# BitBeacon.net
KiCad netlist of a schematic drawn in EAGLE
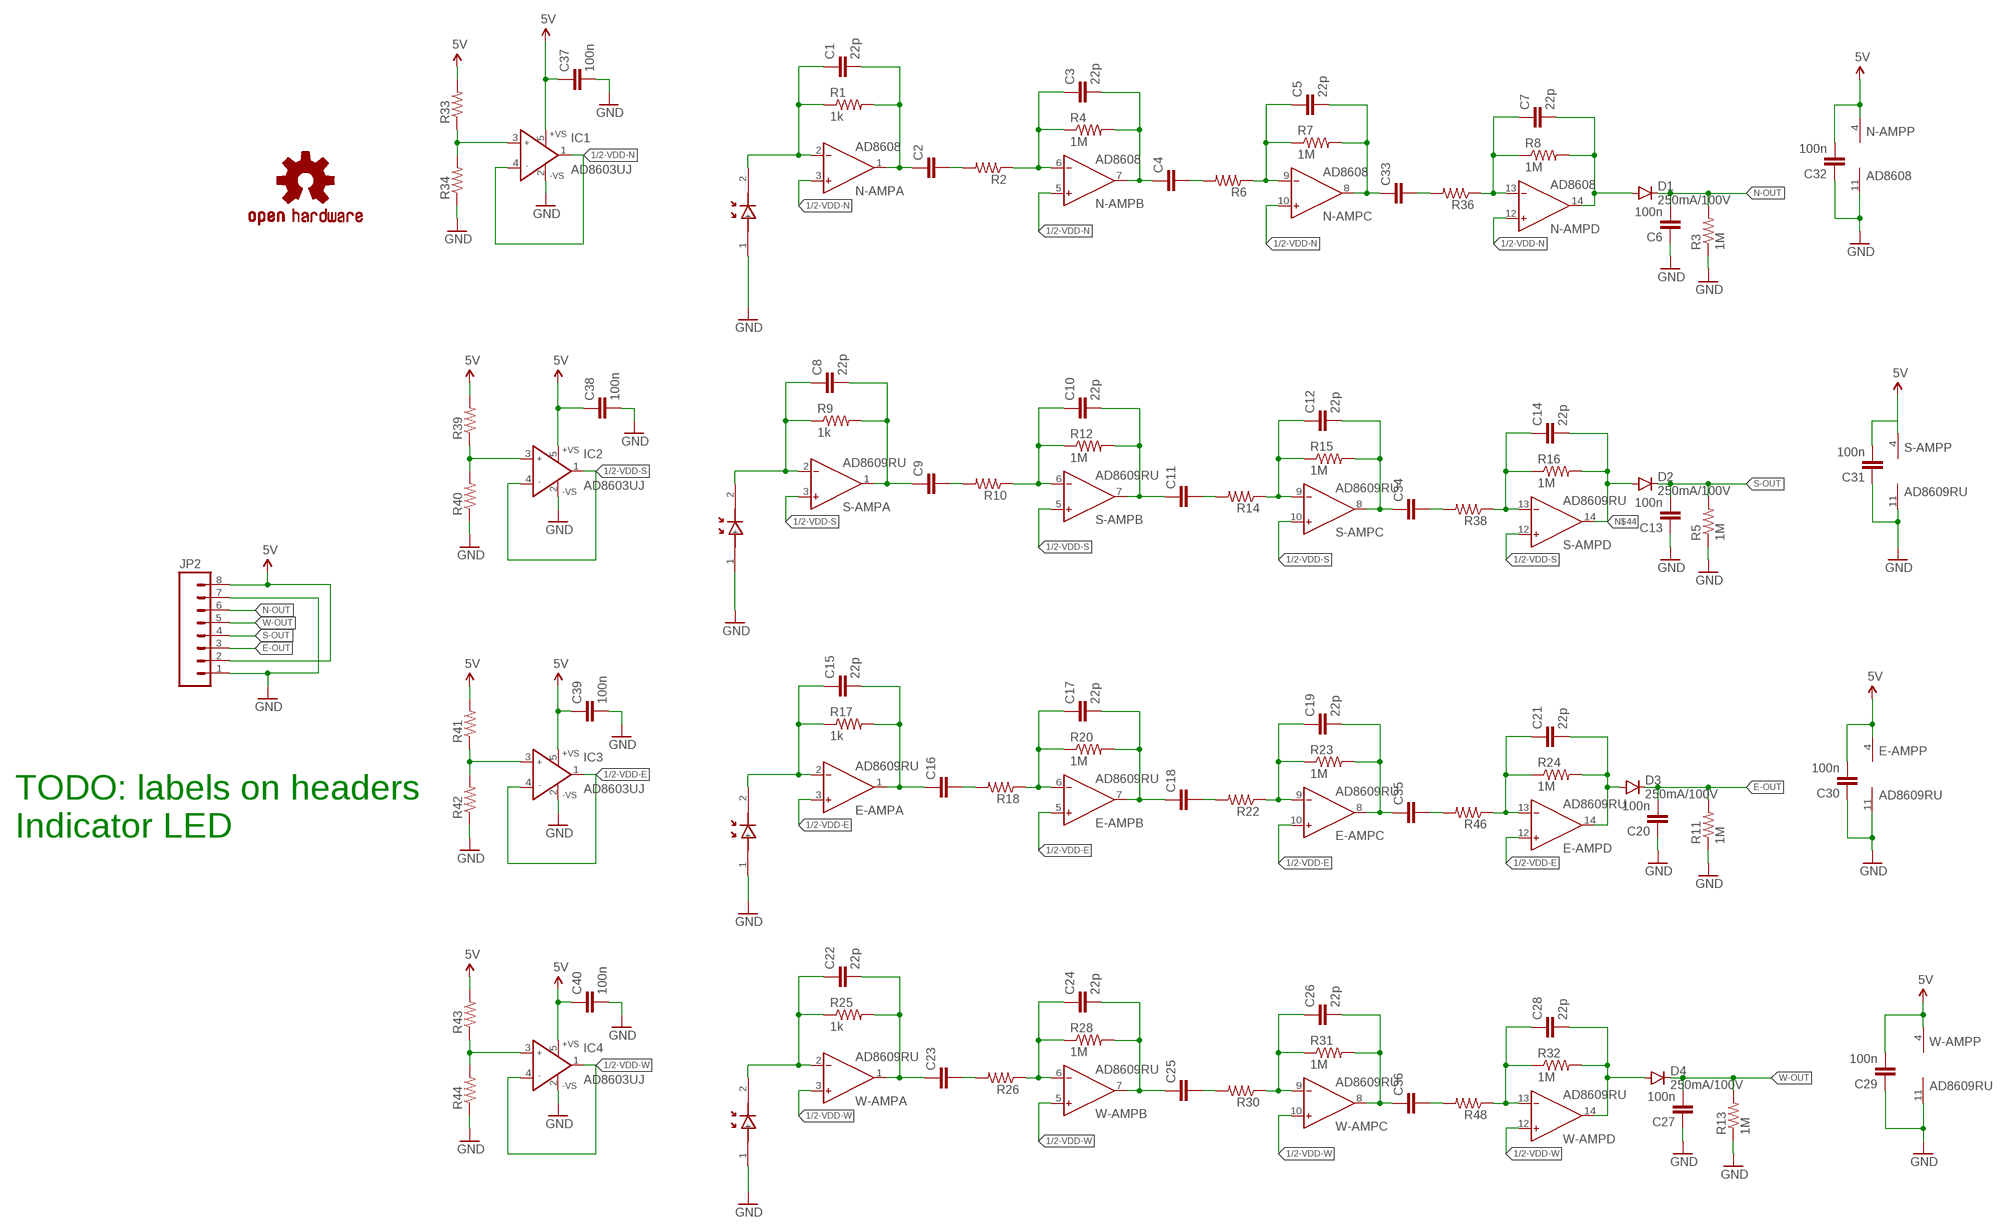
[diagram p0: schematic, sheet 1]

(export (version "E")
  (design (tool "Eeschema 10.0.6"))
  (components
    (comp (ref "C1")
      (value "22p")
      (footprint "eagle-import:C0402")
      (libsource (lib "eagle-import") (part "C-EUC0402"))
    )
    (comp (ref "C2")
      (value "C-EUC0402")
      (footprint "eagle-import:C0402")
      (libsource (lib "eagle-import") (part "C-EUC0402"))
    )
    (comp (ref "C3")
      (value "22p")
      (footprint "eagle-import:C0402")
      (libsource (lib "eagle-import") (part "C-EUC0402"))
    )
    (comp (ref "C4")
      (value "C-EUC0402")
      (footprint "eagle-import:C0402")
      (libsource (lib "eagle-import") (part "C-EUC0402"))
    )
    (comp (ref "C5")
      (value "22p")
      (footprint "eagle-import:C0402")
      (libsource (lib "eagle-import") (part "C-EUC0402"))
    )
    (comp (ref "C6")
      (value "100n")
      (footprint "eagle-import:C0402")
      (libsource (lib "eagle-import") (part "C-EUC0402"))
    )
    (comp (ref "C7")
      (value "22p")
      (footprint "eagle-import:C0402")
      (libsource (lib "eagle-import") (part "C-EUC0402"))
    )
    (comp (ref "C8")
      (value "22p")
      (footprint "eagle-import:C0402")
      (libsource (lib "eagle-import") (part "C-EUC0402"))
    )
    (comp (ref "C9")
      (value "C-EUC0402")
      (footprint "eagle-import:C0402")
      (libsource (lib "eagle-import") (part "C-EUC0402"))
    )
    (comp (ref "C10")
      (value "22p")
      (footprint "eagle-import:C0402")
      (libsource (lib "eagle-import") (part "C-EUC0402"))
    )
    (comp (ref "C11")
      (value "C-EUC0402")
      (footprint "eagle-import:C0402")
      (libsource (lib "eagle-import") (part "C-EUC0402"))
    )
    (comp (ref "C12")
      (value "22p")
      (footprint "eagle-import:C0402")
      (libsource (lib "eagle-import") (part "C-EUC0402"))
    )
    (comp (ref "C13")
      (value "100n")
      (footprint "eagle-import:C0402")
      (libsource (lib "eagle-import") (part "C-EUC0402"))
    )
    (comp (ref "C14")
      (value "22p")
      (footprint "eagle-import:C0402")
      (libsource (lib "eagle-import") (part "C-EUC0402"))
    )
    (comp (ref "C15")
      (value "22p")
      (footprint "eagle-import:C0402")
      (libsource (lib "eagle-import") (part "C-EUC0402"))
    )
    (comp (ref "C16")
      (value "C-EUC0402")
      (footprint "eagle-import:C0402")
      (libsource (lib "eagle-import") (part "C-EUC0402"))
    )
    (comp (ref "C17")
      (value "22p")
      (footprint "eagle-import:C0402")
      (libsource (lib "eagle-import") (part "C-EUC0402"))
    )
    (comp (ref "C18")
      (value "C-EUC0402")
      (footprint "eagle-import:C0402")
      (libsource (lib "eagle-import") (part "C-EUC0402"))
    )
    (comp (ref "C19")
      (value "22p")
      (footprint "eagle-import:C0402")
      (libsource (lib "eagle-import") (part "C-EUC0402"))
    )
    (comp (ref "C20")
      (value "100n")
      (footprint "eagle-import:C0402")
      (libsource (lib "eagle-import") (part "C-EUC0402"))
    )
    (comp (ref "C21")
      (value "22p")
      (footprint "eagle-import:C0402")
      (libsource (lib "eagle-import") (part "C-EUC0402"))
    )
    (comp (ref "C22")
      (value "22p")
      (footprint "eagle-import:C0402")
      (libsource (lib "eagle-import") (part "C-EUC0402"))
    )
    (comp (ref "C23")
      (value "C-EUC0402")
      (footprint "eagle-import:C0402")
      (libsource (lib "eagle-import") (part "C-EUC0402"))
    )
    (comp (ref "C24")
      (value "22p")
      (footprint "eagle-import:C0402")
      (libsource (lib "eagle-import") (part "C-EUC0402"))
    )
    (comp (ref "C25")
      (value "C-EUC0402")
      (footprint "eagle-import:C0402")
      (libsource (lib "eagle-import") (part "C-EUC0402"))
    )
    (comp (ref "C26")
      (value "22p")
      (footprint "eagle-import:C0402")
      (libsource (lib "eagle-import") (part "C-EUC0402"))
    )
    (comp (ref "C27")
      (value "100n")
      (footprint "eagle-import:C0402")
      (libsource (lib "eagle-import") (part "C-EUC0402"))
    )
    (comp (ref "C28")
      (value "22p")
      (footprint "eagle-import:C0402")
      (libsource (lib "eagle-import") (part "C-EUC0402"))
    )
    (comp (ref "C29")
      (value "100n")
      (footprint "eagle-import:C0402")
      (libsource (lib "eagle-import") (part "C-EUC0402"))
    )
    (comp (ref "C30")
      (value "100n")
      (footprint "eagle-import:C0402")
      (libsource (lib "eagle-import") (part "C-EUC0402"))
    )
    (comp (ref "C31")
      (value "100n")
      (footprint "eagle-import:C0402")
      (libsource (lib "eagle-import") (part "C-EUC0402"))
    )
    (comp (ref "C32")
      (value "100n")
      (footprint "eagle-import:C0402")
      (libsource (lib "eagle-import") (part "C-EUC0402"))
    )
    (comp (ref "C33")
      (value "C-EUC0402")
      (footprint "eagle-import:C0402")
      (libsource (lib "eagle-import") (part "C-EUC0402"))
    )
    (comp (ref "C34")
      (value "C-EUC0402")
      (footprint "eagle-import:C0402")
      (libsource (lib "eagle-import") (part "C-EUC0402"))
    )
    (comp (ref "C35")
      (value "C-EUC0402")
      (footprint "eagle-import:C0402")
      (libsource (lib "eagle-import") (part "C-EUC0402"))
    )
    (comp (ref "C36")
      (value "C-EUC0402")
      (footprint "eagle-import:C0402")
      (libsource (lib "eagle-import") (part "C-EUC0402"))
    )
    (comp (ref "C37")
      (value "100n")
      (footprint "eagle-import:C0402")
      (libsource (lib "eagle-import") (part "C-EUC0402"))
    )
    (comp (ref "C38")
      (value "100n")
      (footprint "eagle-import:C0402")
      (libsource (lib "eagle-import") (part "C-EUC0402"))
    )
    (comp (ref "C39")
      (value "100n")
      (footprint "eagle-import:C0402")
      (libsource (lib "eagle-import") (part "C-EUC0402"))
    )
    (comp (ref "C40")
      (value "100n")
      (footprint "eagle-import:C0402")
      (libsource (lib "eagle-import") (part "C-EUC0402"))
    )
    (comp (ref "D1")
      (value "250mA/100V")
      (footprint "eagle-import:SOD-323")
      (libsource (lib "eagle-import") (part "DIODEBAS16"))
    )
    (comp (ref "D2")
      (value "250mA/100V")
      (footprint "eagle-import:SOD-323")
      (libsource (lib "eagle-import") (part "DIODEBAS16"))
    )
    (comp (ref "D3")
      (value "250mA/100V")
      (footprint "eagle-import:SOD-323")
      (libsource (lib "eagle-import") (part "DIODEBAS16"))
    )
    (comp (ref "D4")
      (value "250mA/100V")
      (footprint "eagle-import:SOD-323")
      (libsource (lib "eagle-import") (part "DIODEBAS16"))
    )
    (comp (ref "E-AMP")
      (value "AD8609RU")
      (footprint "eagle-import:TSSOP14")
      (fields (field (name "MF") "ALTERA CORPORATION") (field (name "MPN") "AD8609ARUZ"))
      (libsource (lib "eagle-import") (part "AD8609RU"))
    )
    (comp (ref "E-PD1")
      (value "BPW46")
      (footprint "eagle-import:PIN-PHOTODIODE")
      (libsource (lib "eagle-import") (part "BPW46"))
    )
    (comp (ref "IC1")
      (value "AD8603UJ")
      (footprint "eagle-import:SOT23-5")
      (fields (field (name "MF") "ALTERA CORPORATION") (field (name "MPN") "AD8603AUJZ-REEL7"))
      (libsource (lib "eagle-import") (part "AD8603UJ"))
    )
    (comp (ref "IC2")
      (value "AD8603UJ")
      (footprint "eagle-import:SOT23-5")
      (fields (field (name "MF") "ALTERA CORPORATION") (field (name "MPN") "AD8603AUJZ-REEL7"))
      (libsource (lib "eagle-import") (part "AD8603UJ"))
    )
    (comp (ref "IC3")
      (value "AD8603UJ")
      (footprint "eagle-import:SOT23-5")
      (fields (field (name "MF") "ALTERA CORPORATION") (field (name "MPN") "AD8603AUJZ-REEL7"))
      (libsource (lib "eagle-import") (part "AD8603UJ"))
    )
    (comp (ref "IC4")
      (value "AD8603UJ")
      (footprint "eagle-import:SOT23-5")
      (fields (field (name "MF") "ALTERA CORPORATION") (field (name "MPN") "AD8603AUJZ-REEL7"))
      (libsource (lib "eagle-import") (part "AD8603UJ"))
    )
    (comp (ref "JP2")
      (value "M08NO_SILK")
      (footprint "eagle-import:1X08_PIN1_NO_SILK")
      (libsource (lib "eagle-import") (part "M08NO_SILK"))
    )
    (comp (ref "LOGO1")
      (value "OSHW-LOGOS")
      (footprint "eagle-import:OSHW-LOGO-S")
      (libsource (lib "eagle-import") (part "OSHW-LOGOS"))
    )
    (comp (ref "N-AMP")
      (value "AD8608")
      (footprint "eagle-import:TSSOP14")
      (fields (field (name "MF") "ALTERA CORPORATION") (field (name "MPN") "AD8609ARUZ"))
      (libsource (lib "eagle-import") (part "AD8609RU"))
    )
    (comp (ref "N-PD1")
      (value "BPW46")
      (footprint "eagle-import:PIN-PHOTODIODE")
      (libsource (lib "eagle-import") (part "BPW46"))
    )
    (comp (ref "R1")
      (value "1k")
      (footprint "eagle-import:R0402")
      (libsource (lib "eagle-import") (part "R-US_R0402"))
    )
    (comp (ref "R2")
      (value "R-US_R0402")
      (footprint "eagle-import:R0402")
      (libsource (lib "eagle-import") (part "R-US_R0402"))
    )
    (comp (ref "R3")
      (value "1M")
      (footprint "eagle-import:R0402")
      (libsource (lib "eagle-import") (part "R-US_R0402"))
    )
    (comp (ref "R4")
      (value "1M")
      (footprint "eagle-import:R0402")
      (libsource (lib "eagle-import") (part "R-US_R0402"))
    )
    (comp (ref "R5")
      (value "1M")
      (footprint "eagle-import:R0402")
      (libsource (lib "eagle-import") (part "R-US_R0402"))
    )
    (comp (ref "R6")
      (value "R-US_R0402")
      (footprint "eagle-import:R0402")
      (libsource (lib "eagle-import") (part "R-US_R0402"))
    )
    (comp (ref "R7")
      (value "1M")
      (footprint "eagle-import:R0402")
      (libsource (lib "eagle-import") (part "R-US_R0402"))
    )
    (comp (ref "R8")
      (value "1M")
      (footprint "eagle-import:R0402")
      (libsource (lib "eagle-import") (part "R-US_R0402"))
    )
    (comp (ref "R9")
      (value "1k")
      (footprint "eagle-import:R0402")
      (libsource (lib "eagle-import") (part "R-US_R0402"))
    )
    (comp (ref "R10")
      (value "R-US_R0402")
      (footprint "eagle-import:R0402")
      (libsource (lib "eagle-import") (part "R-US_R0402"))
    )
    (comp (ref "R11")
      (value "1M")
      (footprint "eagle-import:R0402")
      (libsource (lib "eagle-import") (part "R-US_R0402"))
    )
    (comp (ref "R12")
      (value "1M")
      (footprint "eagle-import:R0402")
      (libsource (lib "eagle-import") (part "R-US_R0402"))
    )
    (comp (ref "R13")
      (value "1M")
      (footprint "eagle-import:R0402")
      (libsource (lib "eagle-import") (part "R-US_R0402"))
    )
    (comp (ref "R14")
      (value "R-US_R0402")
      (footprint "eagle-import:R0402")
      (libsource (lib "eagle-import") (part "R-US_R0402"))
    )
    (comp (ref "R15")
      (value "1M")
      (footprint "eagle-import:R0402")
      (libsource (lib "eagle-import") (part "R-US_R0402"))
    )
    (comp (ref "R16")
      (value "1M")
      (footprint "eagle-import:R0402")
      (libsource (lib "eagle-import") (part "R-US_R0402"))
    )
    (comp (ref "R17")
      (value "1k")
      (footprint "eagle-import:R0402")
      (libsource (lib "eagle-import") (part "R-US_R0402"))
    )
    (comp (ref "R18")
      (value "R-US_R0402")
      (footprint "eagle-import:R0402")
      (libsource (lib "eagle-import") (part "R-US_R0402"))
    )
    (comp (ref "R20")
      (value "1M")
      (footprint "eagle-import:R0402")
      (libsource (lib "eagle-import") (part "R-US_R0402"))
    )
    (comp (ref "R22")
      (value "R-US_R0402")
      (footprint "eagle-import:R0402")
      (libsource (lib "eagle-import") (part "R-US_R0402"))
    )
    (comp (ref "R23")
      (value "1M")
      (footprint "eagle-import:R0402")
      (libsource (lib "eagle-import") (part "R-US_R0402"))
    )
    (comp (ref "R24")
      (value "1M")
      (footprint "eagle-import:R0402")
      (libsource (lib "eagle-import") (part "R-US_R0402"))
    )
    (comp (ref "R25")
      (value "1k")
      (footprint "eagle-import:R0402")
      (libsource (lib "eagle-import") (part "R-US_R0402"))
    )
    (comp (ref "R26")
      (value "R-US_R0402")
      (footprint "eagle-import:R0402")
      (libsource (lib "eagle-import") (part "R-US_R0402"))
    )
    (comp (ref "R28")
      (value "1M")
      (footprint "eagle-import:R0402")
      (libsource (lib "eagle-import") (part "R-US_R0402"))
    )
    (comp (ref "R30")
      (value "R-US_R0402")
      (footprint "eagle-import:R0402")
      (libsource (lib "eagle-import") (part "R-US_R0402"))
    )
    (comp (ref "R31")
      (value "1M")
      (footprint "eagle-import:R0402")
      (libsource (lib "eagle-import") (part "R-US_R0402"))
    )
    (comp (ref "R32")
      (value "1M")
      (footprint "eagle-import:R0402")
      (libsource (lib "eagle-import") (part "R-US_R0402"))
    )
    (comp (ref "R33")
      (value "R-US_R0402")
      (footprint "eagle-import:R0402")
      (libsource (lib "eagle-import") (part "R-US_R0402"))
    )
    (comp (ref "R34")
      (value "R-US_R0402")
      (footprint "eagle-import:R0402")
      (libsource (lib "eagle-import") (part "R-US_R0402"))
    )
    (comp (ref "R36")
      (value "R-US_R0402")
      (footprint "eagle-import:R0402")
      (libsource (lib "eagle-import") (part "R-US_R0402"))
    )
    (comp (ref "R38")
      (value "R-US_R0402")
      (footprint "eagle-import:R0402")
      (libsource (lib "eagle-import") (part "R-US_R0402"))
    )
    (comp (ref "R39")
      (value "R-US_R0402")
      (footprint "eagle-import:R0402")
      (libsource (lib "eagle-import") (part "R-US_R0402"))
    )
    (comp (ref "R40")
      (value "R-US_R0402")
      (footprint "eagle-import:R0402")
      (libsource (lib "eagle-import") (part "R-US_R0402"))
    )
    (comp (ref "R41")
      (value "R-US_R0402")
      (footprint "eagle-import:R0402")
      (libsource (lib "eagle-import") (part "R-US_R0402"))
    )
    (comp (ref "R42")
      (value "R-US_R0402")
      (footprint "eagle-import:R0402")
      (libsource (lib "eagle-import") (part "R-US_R0402"))
    )
    (comp (ref "R43")
      (value "R-US_R0402")
      (footprint "eagle-import:R0402")
      (libsource (lib "eagle-import") (part "R-US_R0402"))
    )
    (comp (ref "R44")
      (value "R-US_R0402")
      (footprint "eagle-import:R0402")
      (libsource (lib "eagle-import") (part "R-US_R0402"))
    )
    (comp (ref "R46")
      (value "R-US_R0402")
      (footprint "eagle-import:R0402")
      (libsource (lib "eagle-import") (part "R-US_R0402"))
    )
    (comp (ref "R48")
      (value "R-US_R0402")
      (footprint "eagle-import:R0402")
      (libsource (lib "eagle-import") (part "R-US_R0402"))
    )
    (comp (ref "S-AMP")
      (value "AD8609RU")
      (footprint "eagle-import:TSSOP14")
      (fields (field (name "MF") "ALTERA CORPORATION") (field (name "MPN") "AD8609ARUZ"))
      (libsource (lib "eagle-import") (part "AD8609RU"))
    )
    (comp (ref "S-PD1")
      (value "BPW46")
      (footprint "eagle-import:PIN-PHOTODIODE")
      (libsource (lib "eagle-import") (part "BPW46"))
    )
    (comp (ref "W-AMP")
      (value "AD8609RU")
      (footprint "eagle-import:TSSOP14")
      (fields (field (name "MF") "ALTERA CORPORATION") (field (name "MPN") "AD8609ARUZ"))
      (libsource (lib "eagle-import") (part "AD8609RU"))
    )
    (comp (ref "W-PD1")
      (value "BPW46")
      (footprint "eagle-import:PIN-PHOTODIODE")
      (libsource (lib "eagle-import") (part "BPW46"))
    )
  )
  (nets
    (net (code "1") (name "1{slash}2-VDD-E") (class "Default")
      (node (ref "E-AMP") (pin "10") (pinfunction "IN+_10") (pintype "input"))
      (node (ref "E-AMP") (pin "12") (pinfunction "IN+_12") (pintype "input"))
      (node (ref "E-AMP") (pin "3") (pinfunction "IN+_3") (pintype "input"))
      (node (ref "E-AMP") (pin "5") (pinfunction "IN+_5") (pintype "input"))
      (node (ref "IC3") (pin "1") (pinfunction "OUT_1") (pintype "output"))
      (node (ref "IC3") (pin "4") (pinfunction "IN-_4") (pintype "input"))
    )
    (net (code "2") (name "1{slash}2-VDD-N") (class "Default")
      (node (ref "IC1") (pin "1") (pinfunction "OUT_1") (pintype "output"))
      (node (ref "IC1") (pin "4") (pinfunction "IN-_4") (pintype "input"))
      (node (ref "N-AMP") (pin "10") (pinfunction "IN+_10") (pintype "input"))
      (node (ref "N-AMP") (pin "12") (pinfunction "IN+_12") (pintype "input"))
      (node (ref "N-AMP") (pin "3") (pinfunction "IN+_3") (pintype "input"))
      (node (ref "N-AMP") (pin "5") (pinfunction "IN+_5") (pintype "input"))
    )
    (net (code "3") (name "1{slash}2-VDD-S") (class "Default")
      (node (ref "IC2") (pin "1") (pinfunction "OUT_1") (pintype "output"))
      (node (ref "IC2") (pin "4") (pinfunction "IN-_4") (pintype "input"))
      (node (ref "S-AMP") (pin "10") (pinfunction "IN+_10") (pintype "input"))
      (node (ref "S-AMP") (pin "12") (pinfunction "IN+_12") (pintype "input"))
      (node (ref "S-AMP") (pin "3") (pinfunction "IN+_3") (pintype "input"))
      (node (ref "S-AMP") (pin "5") (pinfunction "IN+_5") (pintype "input"))
    )
    (net (code "4") (name "1{slash}2-VDD-W") (class "Default")
      (node (ref "IC4") (pin "1") (pinfunction "OUT_1") (pintype "output"))
      (node (ref "IC4") (pin "4") (pinfunction "IN-_4") (pintype "input"))
      (node (ref "W-AMP") (pin "10") (pinfunction "IN+_10") (pintype "input"))
      (node (ref "W-AMP") (pin "12") (pinfunction "IN+_12") (pintype "input"))
      (node (ref "W-AMP") (pin "3") (pinfunction "IN+_3") (pintype "input"))
      (node (ref "W-AMP") (pin "5") (pinfunction "IN+_5") (pintype "input"))
    )
    (net (code "5") (name "5V") (class "Default")
      (node (ref "C29") (pin "2") (pinfunction "2_2") (pintype "passive"))
      (node (ref "C30") (pin "2") (pinfunction "2_2") (pintype "passive"))
      (node (ref "C31") (pin "2") (pinfunction "2_2") (pintype "passive"))
      (node (ref "C32") (pin "2") (pinfunction "2_2") (pintype "passive"))
      (node (ref "C37") (pin "1") (pinfunction "1_1") (pintype "passive"))
      (node (ref "C38") (pin "1") (pinfunction "1_1") (pintype "passive"))
      (node (ref "C39") (pin "1") (pinfunction "1_1") (pintype "passive"))
      (node (ref "C40") (pin "1") (pinfunction "1_1") (pintype "passive"))
      (node (ref "E-AMP") (pin "4") (pinfunction "V+_4") (pintype "power_in"))
      (node (ref "IC1") (pin "5") (pinfunction "+VS_5") (pintype "input"))
      (node (ref "IC2") (pin "5") (pinfunction "+VS_5") (pintype "input"))
      (node (ref "IC3") (pin "5") (pinfunction "+VS_5") (pintype "input"))
      (node (ref "IC4") (pin "5") (pinfunction "+VS_5") (pintype "input"))
      (node (ref "JP2") (pin "2") (pinfunction "2_2") (pintype "passive"))
      (node (ref "JP2") (pin "8") (pinfunction "8_8") (pintype "passive"))
      (node (ref "N-AMP") (pin "4") (pinfunction "V+_4") (pintype "power_in"))
      (node (ref "R33") (pin "2") (pinfunction "2_2") (pintype "passive"))
      (node (ref "R39") (pin "2") (pinfunction "2_2") (pintype "passive"))
      (node (ref "R41") (pin "2") (pinfunction "2_2") (pintype "passive"))
      (node (ref "R43") (pin "2") (pinfunction "2_2") (pintype "passive"))
      (node (ref "S-AMP") (pin "4") (pinfunction "V+_4") (pintype "power_in"))
      (node (ref "W-AMP") (pin "4") (pinfunction "V+_4") (pintype "power_in"))
    )
    (net (code "6") (name "E-OUT") (class "Default")
      (node (ref "C20") (pin "2") (pinfunction "2_2") (pintype "passive"))
      (node (ref "D3") (pin "C") (pinfunction "C_C") (pintype "passive"))
      (node (ref "JP2") (pin "3") (pinfunction "3_3") (pintype "passive"))
      (node (ref "R11") (pin "2") (pinfunction "2_2") (pintype "passive"))
    )
    (net (code "7") (name "GND") (class "Default")
      (node (ref "C13") (pin "1") (pinfunction "1_1") (pintype "passive"))
      (node (ref "C20") (pin "1") (pinfunction "1_1") (pintype "passive"))
      (node (ref "C27") (pin "1") (pinfunction "1_1") (pintype "passive"))
      (node (ref "C29") (pin "1") (pinfunction "1_1") (pintype "passive"))
      (node (ref "C30") (pin "1") (pinfunction "1_1") (pintype "passive"))
      (node (ref "C31") (pin "1") (pinfunction "1_1") (pintype "passive"))
      (node (ref "C32") (pin "1") (pinfunction "1_1") (pintype "passive"))
      (node (ref "C37") (pin "2") (pinfunction "2_2") (pintype "passive"))
      (node (ref "C38") (pin "2") (pinfunction "2_2") (pintype "passive"))
      (node (ref "C39") (pin "2") (pinfunction "2_2") (pintype "passive"))
      (node (ref "C40") (pin "2") (pinfunction "2_2") (pintype "passive"))
      (node (ref "C6") (pin "1") (pinfunction "1_1") (pintype "passive"))
      (node (ref "E-AMP") (pin "11") (pinfunction "V-_11") (pintype "power_in"))
      (node (ref "E-PD1") (pin "1") (pinfunction "+_1") (pintype "bidirectional"))
      (node (ref "IC1") (pin "2") (pinfunction "-VS_2") (pintype "input"))
      (node (ref "IC2") (pin "2") (pinfunction "-VS_2") (pintype "input"))
      (node (ref "IC3") (pin "2") (pinfunction "-VS_2") (pintype "input"))
      (node (ref "IC4") (pin "2") (pinfunction "-VS_2") (pintype "input"))
      (node (ref "JP2") (pin "1") (pinfunction "1_1") (pintype "passive"))
      (node (ref "JP2") (pin "7") (pinfunction "7_7") (pintype "passive"))
      (node (ref "N-AMP") (pin "11") (pinfunction "V-_11") (pintype "power_in"))
      (node (ref "N-PD1") (pin "1") (pinfunction "+_1") (pintype "bidirectional"))
      (node (ref "R11") (pin "1") (pinfunction "1_1") (pintype "passive"))
      (node (ref "R13") (pin "1") (pinfunction "1_1") (pintype "passive"))
      (node (ref "R3") (pin "1") (pinfunction "1_1") (pintype "passive"))
      (node (ref "R34") (pin "1") (pinfunction "1_1") (pintype "passive"))
      (node (ref "R40") (pin "1") (pinfunction "1_1") (pintype "passive"))
      (node (ref "R42") (pin "1") (pinfunction "1_1") (pintype "passive"))
      (node (ref "R44") (pin "1") (pinfunction "1_1") (pintype "passive"))
      (node (ref "R5") (pin "1") (pinfunction "1_1") (pintype "passive"))
      (node (ref "S-AMP") (pin "11") (pinfunction "V-_11") (pintype "power_in"))
      (node (ref "S-PD1") (pin "1") (pinfunction "+_1") (pintype "bidirectional"))
      (node (ref "W-AMP") (pin "11") (pinfunction "V-_11") (pintype "power_in"))
      (node (ref "W-PD1") (pin "1") (pinfunction "+_1") (pintype "bidirectional"))
    )
    (net (code "8") (name "N$44") (class "Default")
      (node (ref "C14") (pin "2") (pinfunction "2_2") (pintype "passive"))
      (node (ref "D2") (pin "A") (pinfunction "A_A") (pintype "passive"))
      (node (ref "R16") (pin "2") (pinfunction "2_2") (pintype "passive"))
      (node (ref "S-AMP") (pin "14") (pinfunction "OUT_14") (pintype "output"))
    )
    (net (code "9") (name "N-OUT") (class "Default")
      (node (ref "C6") (pin "2") (pinfunction "2_2") (pintype "passive"))
      (node (ref "D1") (pin "C") (pinfunction "C_C") (pintype "passive"))
      (node (ref "JP2") (pin "6") (pinfunction "6_6") (pintype "passive"))
      (node (ref "R3") (pin "2") (pinfunction "2_2") (pintype "passive"))
    )
    (net (code "10") (name "Net-(C2-Pad2)") (class "Default")
      (node (ref "C2") (pin "2") (pinfunction "2_2") (pintype "passive"))
      (node (ref "R2") (pin "2") (pinfunction "2_2") (pintype "passive"))
    )
    (net (code "11") (name "Net-(C4-Pad2)") (class "Default")
      (node (ref "C4") (pin "2") (pinfunction "2_2") (pintype "passive"))
      (node (ref "R6") (pin "2") (pinfunction "2_2") (pintype "passive"))
    )
    (net (code "12") (name "Net-(C9-Pad2)") (class "Default")
      (node (ref "C9") (pin "2") (pinfunction "2_2") (pintype "passive"))
      (node (ref "R10") (pin "2") (pinfunction "2_2") (pintype "passive"))
    )
    (net (code "13") (name "Net-(C11-Pad2)") (class "Default")
      (node (ref "C11") (pin "2") (pinfunction "2_2") (pintype "passive"))
      (node (ref "R14") (pin "2") (pinfunction "2_2") (pintype "passive"))
    )
    (net (code "14") (name "Net-(C16-Pad2)") (class "Default")
      (node (ref "C16") (pin "2") (pinfunction "2_2") (pintype "passive"))
      (node (ref "R18") (pin "2") (pinfunction "2_2") (pintype "passive"))
    )
    (net (code "15") (name "Net-(C18-Pad2)") (class "Default")
      (node (ref "C18") (pin "2") (pinfunction "2_2") (pintype "passive"))
      (node (ref "R22") (pin "2") (pinfunction "2_2") (pintype "passive"))
    )
    (net (code "16") (name "Net-(C23-Pad2)") (class "Default")
      (node (ref "C23") (pin "2") (pinfunction "2_2") (pintype "passive"))
      (node (ref "R26") (pin "2") (pinfunction "2_2") (pintype "passive"))
    )
    (net (code "17") (name "Net-(C25-Pad2)") (class "Default")
      (node (ref "C25") (pin "2") (pinfunction "2_2") (pintype "passive"))
      (node (ref "R30") (pin "2") (pinfunction "2_2") (pintype "passive"))
    )
    (net (code "18") (name "Net-(C33-Pad2)") (class "Default")
      (node (ref "C33") (pin "2") (pinfunction "2_2") (pintype "passive"))
      (node (ref "R36") (pin "2") (pinfunction "2_2") (pintype "passive"))
    )
    (net (code "19") (name "Net-(C34-Pad2)") (class "Default")
      (node (ref "C34") (pin "2") (pinfunction "2_2") (pintype "passive"))
      (node (ref "R38") (pin "2") (pinfunction "2_2") (pintype "passive"))
    )
    (net (code "20") (name "Net-(C35-Pad2)") (class "Default")
      (node (ref "C35") (pin "2") (pinfunction "2_2") (pintype "passive"))
      (node (ref "R46") (pin "2") (pinfunction "2_2") (pintype "passive"))
    )
    (net (code "21") (name "Net-(C36-Pad2)") (class "Default")
      (node (ref "C36") (pin "2") (pinfunction "2_2") (pintype "passive"))
      (node (ref "R48") (pin "2") (pinfunction "2_2") (pintype "passive"))
    )
    (net (code "22") (name "Net-(E-AMPA-IN-)") (class "Default")
      (node (ref "C15") (pin "1") (pinfunction "1_1") (pintype "passive"))
      (node (ref "E-AMP") (pin "2") (pinfunction "IN-_2") (pintype "input"))
      (node (ref "E-PD1") (pin "2") (pinfunction "-_2") (pintype "bidirectional"))
      (node (ref "R17") (pin "1") (pinfunction "1_1") (pintype "passive"))
    )
    (net (code "23") (name "Net-(E-AMPA-OUT)") (class "Default")
      (node (ref "C15") (pin "2") (pinfunction "2_2") (pintype "passive"))
      (node (ref "C16") (pin "1") (pinfunction "1_1") (pintype "passive"))
      (node (ref "E-AMP") (pin "1") (pinfunction "OUT_1") (pintype "output"))
      (node (ref "R17") (pin "2") (pinfunction "2_2") (pintype "passive"))
    )
    (net (code "24") (name "Net-(E-AMPB-IN-)") (class "Default")
      (node (ref "C17") (pin "1") (pinfunction "1_1") (pintype "passive"))
      (node (ref "E-AMP") (pin "6") (pinfunction "IN-_6") (pintype "input"))
      (node (ref "R18") (pin "1") (pinfunction "1_1") (pintype "passive"))
      (node (ref "R20") (pin "1") (pinfunction "1_1") (pintype "passive"))
    )
    (net (code "25") (name "Net-(E-AMPB-OUT)") (class "Default")
      (node (ref "C17") (pin "2") (pinfunction "2_2") (pintype "passive"))
      (node (ref "C18") (pin "1") (pinfunction "1_1") (pintype "passive"))
      (node (ref "E-AMP") (pin "7") (pinfunction "OUT_7") (pintype "output"))
      (node (ref "R20") (pin "2") (pinfunction "2_2") (pintype "passive"))
    )
    (net (code "26") (name "Net-(E-AMPC-IN-)") (class "Default")
      (node (ref "C19") (pin "1") (pinfunction "1_1") (pintype "passive"))
      (node (ref "E-AMP") (pin "9") (pinfunction "IN-_9") (pintype "input"))
      (node (ref "R22") (pin "1") (pinfunction "1_1") (pintype "passive"))
      (node (ref "R23") (pin "1") (pinfunction "1_1") (pintype "passive"))
    )
    (net (code "27") (name "Net-(E-AMPC-OUT)") (class "Default")
      (node (ref "C19") (pin "2") (pinfunction "2_2") (pintype "passive"))
      (node (ref "C35") (pin "1") (pinfunction "1_1") (pintype "passive"))
      (node (ref "E-AMP") (pin "8") (pinfunction "OUT_8") (pintype "output"))
      (node (ref "R23") (pin "2") (pinfunction "2_2") (pintype "passive"))
    )
    (net (code "28") (name "Net-(E-AMPD-IN-)") (class "Default")
      (node (ref "C21") (pin "1") (pinfunction "1_1") (pintype "passive"))
      (node (ref "E-AMP") (pin "13") (pinfunction "IN-_13") (pintype "input"))
      (node (ref "R24") (pin "1") (pinfunction "1_1") (pintype "passive"))
      (node (ref "R46") (pin "1") (pinfunction "1_1") (pintype "passive"))
    )
    (net (code "29") (name "Net-(E-AMPD-OUT)") (class "Default")
      (node (ref "C21") (pin "2") (pinfunction "2_2") (pintype "passive"))
      (node (ref "D3") (pin "A") (pinfunction "A_A") (pintype "passive"))
      (node (ref "E-AMP") (pin "14") (pinfunction "OUT_14") (pintype "output"))
      (node (ref "R24") (pin "2") (pinfunction "2_2") (pintype "passive"))
    )
    (net (code "30") (name "Net-(IC1-IN+)") (class "Default")
      (node (ref "IC1") (pin "3") (pinfunction "IN+_3") (pintype "input"))
      (node (ref "R33") (pin "1") (pinfunction "1_1") (pintype "passive"))
      (node (ref "R34") (pin "2") (pinfunction "2_2") (pintype "passive"))
    )
    (net (code "31") (name "Net-(IC2-IN+)") (class "Default")
      (node (ref "IC2") (pin "3") (pinfunction "IN+_3") (pintype "input"))
      (node (ref "R39") (pin "1") (pinfunction "1_1") (pintype "passive"))
      (node (ref "R40") (pin "2") (pinfunction "2_2") (pintype "passive"))
    )
    (net (code "32") (name "Net-(IC3-IN+)") (class "Default")
      (node (ref "IC3") (pin "3") (pinfunction "IN+_3") (pintype "input"))
      (node (ref "R41") (pin "1") (pinfunction "1_1") (pintype "passive"))
      (node (ref "R42") (pin "2") (pinfunction "2_2") (pintype "passive"))
    )
    (net (code "33") (name "Net-(IC4-IN+)") (class "Default")
      (node (ref "IC4") (pin "3") (pinfunction "IN+_3") (pintype "input"))
      (node (ref "R43") (pin "1") (pinfunction "1_1") (pintype "passive"))
      (node (ref "R44") (pin "2") (pinfunction "2_2") (pintype "passive"))
    )
    (net (code "34") (name "Net-(N-AMPA-IN-)") (class "Default")
      (node (ref "C1") (pin "1") (pinfunction "1_1") (pintype "passive"))
      (node (ref "N-AMP") (pin "2") (pinfunction "IN-_2") (pintype "input"))
      (node (ref "N-PD1") (pin "2") (pinfunction "-_2") (pintype "bidirectional"))
      (node (ref "R1") (pin "1") (pinfunction "1_1") (pintype "passive"))
    )
    (net (code "35") (name "Net-(N-AMPA-OUT)") (class "Default")
      (node (ref "C1") (pin "2") (pinfunction "2_2") (pintype "passive"))
      (node (ref "C2") (pin "1") (pinfunction "1_1") (pintype "passive"))
      (node (ref "N-AMP") (pin "1") (pinfunction "OUT_1") (pintype "output"))
      (node (ref "R1") (pin "2") (pinfunction "2_2") (pintype "passive"))
    )
    (net (code "36") (name "Net-(N-AMPB-IN-)") (class "Default")
      (node (ref "C3") (pin "1") (pinfunction "1_1") (pintype "passive"))
      (node (ref "N-AMP") (pin "6") (pinfunction "IN-_6") (pintype "input"))
      (node (ref "R2") (pin "1") (pinfunction "1_1") (pintype "passive"))
      (node (ref "R4") (pin "1") (pinfunction "1_1") (pintype "passive"))
    )
    (net (code "37") (name "Net-(N-AMPB-OUT)") (class "Default")
      (node (ref "C3") (pin "2") (pinfunction "2_2") (pintype "passive"))
      (node (ref "C4") (pin "1") (pinfunction "1_1") (pintype "passive"))
      (node (ref "N-AMP") (pin "7") (pinfunction "OUT_7") (pintype "output"))
      (node (ref "R4") (pin "2") (pinfunction "2_2") (pintype "passive"))
    )
    (net (code "38") (name "Net-(N-AMPC-IN-)") (class "Default")
      (node (ref "C5") (pin "1") (pinfunction "1_1") (pintype "passive"))
      (node (ref "N-AMP") (pin "9") (pinfunction "IN-_9") (pintype "input"))
      (node (ref "R6") (pin "1") (pinfunction "1_1") (pintype "passive"))
      (node (ref "R7") (pin "1") (pinfunction "1_1") (pintype "passive"))
    )
    (net (code "39") (name "Net-(N-AMPC-OUT)") (class "Default")
      (node (ref "C33") (pin "1") (pinfunction "1_1") (pintype "passive"))
      (node (ref "C5") (pin "2") (pinfunction "2_2") (pintype "passive"))
      (node (ref "N-AMP") (pin "8") (pinfunction "OUT_8") (pintype "output"))
      (node (ref "R7") (pin "2") (pinfunction "2_2") (pintype "passive"))
    )
    (net (code "40") (name "Net-(N-AMPD-IN-)") (class "Default")
      (node (ref "C7") (pin "1") (pinfunction "1_1") (pintype "passive"))
      (node (ref "N-AMP") (pin "13") (pinfunction "IN-_13") (pintype "input"))
      (node (ref "R36") (pin "1") (pinfunction "1_1") (pintype "passive"))
      (node (ref "R8") (pin "1") (pinfunction "1_1") (pintype "passive"))
    )
    (net (code "41") (name "Net-(N-AMPD-OUT)") (class "Default")
      (node (ref "C7") (pin "2") (pinfunction "2_2") (pintype "passive"))
      (node (ref "D1") (pin "A") (pinfunction "A_A") (pintype "passive"))
      (node (ref "N-AMP") (pin "14") (pinfunction "OUT_14") (pintype "output"))
      (node (ref "R8") (pin "2") (pinfunction "2_2") (pintype "passive"))
    )
    (net (code "42") (name "Net-(S-AMPA-IN-)") (class "Default")
      (node (ref "C8") (pin "1") (pinfunction "1_1") (pintype "passive"))
      (node (ref "R9") (pin "1") (pinfunction "1_1") (pintype "passive"))
      (node (ref "S-AMP") (pin "2") (pinfunction "IN-_2") (pintype "input"))
      (node (ref "S-PD1") (pin "2") (pinfunction "-_2") (pintype "bidirectional"))
    )
    (net (code "43") (name "Net-(S-AMPA-OUT)") (class "Default")
      (node (ref "C8") (pin "2") (pinfunction "2_2") (pintype "passive"))
      (node (ref "C9") (pin "1") (pinfunction "1_1") (pintype "passive"))
      (node (ref "R9") (pin "2") (pinfunction "2_2") (pintype "passive"))
      (node (ref "S-AMP") (pin "1") (pinfunction "OUT_1") (pintype "output"))
    )
    (net (code "44") (name "Net-(S-AMPB-IN-)") (class "Default")
      (node (ref "C10") (pin "1") (pinfunction "1_1") (pintype "passive"))
      (node (ref "R10") (pin "1") (pinfunction "1_1") (pintype "passive"))
      (node (ref "R12") (pin "1") (pinfunction "1_1") (pintype "passive"))
      (node (ref "S-AMP") (pin "6") (pinfunction "IN-_6") (pintype "input"))
    )
    (net (code "45") (name "Net-(S-AMPB-OUT)") (class "Default")
      (node (ref "C10") (pin "2") (pinfunction "2_2") (pintype "passive"))
      (node (ref "C11") (pin "1") (pinfunction "1_1") (pintype "passive"))
      (node (ref "R12") (pin "2") (pinfunction "2_2") (pintype "passive"))
      (node (ref "S-AMP") (pin "7") (pinfunction "OUT_7") (pintype "output"))
    )
    (net (code "46") (name "Net-(S-AMPC-IN-)") (class "Default")
      (node (ref "C12") (pin "1") (pinfunction "1_1") (pintype "passive"))
      (node (ref "R14") (pin "1") (pinfunction "1_1") (pintype "passive"))
      (node (ref "R15") (pin "1") (pinfunction "1_1") (pintype "passive"))
      (node (ref "S-AMP") (pin "9") (pinfunction "IN-_9") (pintype "input"))
    )
    (net (code "47") (name "Net-(S-AMPC-OUT)") (class "Default")
      (node (ref "C12") (pin "2") (pinfunction "2_2") (pintype "passive"))
      (node (ref "C34") (pin "1") (pinfunction "1_1") (pintype "passive"))
      (node (ref "R15") (pin "2") (pinfunction "2_2") (pintype "passive"))
      (node (ref "S-AMP") (pin "8") (pinfunction "OUT_8") (pintype "output"))
    )
    (net (code "48") (name "Net-(S-AMPD-IN-)") (class "Default")
      (node (ref "C14") (pin "1") (pinfunction "1_1") (pintype "passive"))
      (node (ref "R16") (pin "1") (pinfunction "1_1") (pintype "passive"))
      (node (ref "R38") (pin "1") (pinfunction "1_1") (pintype "passive"))
      (node (ref "S-AMP") (pin "13") (pinfunction "IN-_13") (pintype "input"))
    )
    (net (code "49") (name "Net-(W-AMPA-IN-)") (class "Default")
      (node (ref "C22") (pin "1") (pinfunction "1_1") (pintype "passive"))
      (node (ref "R25") (pin "1") (pinfunction "1_1") (pintype "passive"))
      (node (ref "W-AMP") (pin "2") (pinfunction "IN-_2") (pintype "input"))
      (node (ref "W-PD1") (pin "2") (pinfunction "-_2") (pintype "bidirectional"))
    )
    (net (code "50") (name "Net-(W-AMPA-OUT)") (class "Default")
      (node (ref "C22") (pin "2") (pinfunction "2_2") (pintype "passive"))
      (node (ref "C23") (pin "1") (pinfunction "1_1") (pintype "passive"))
      (node (ref "R25") (pin "2") (pinfunction "2_2") (pintype "passive"))
      (node (ref "W-AMP") (pin "1") (pinfunction "OUT_1") (pintype "output"))
    )
    (net (code "51") (name "Net-(W-AMPB-IN-)") (class "Default")
      (node (ref "C24") (pin "1") (pinfunction "1_1") (pintype "passive"))
      (node (ref "R26") (pin "1") (pinfunction "1_1") (pintype "passive"))
      (node (ref "R28") (pin "1") (pinfunction "1_1") (pintype "passive"))
      (node (ref "W-AMP") (pin "6") (pinfunction "IN-_6") (pintype "input"))
    )
    (net (code "52") (name "Net-(W-AMPB-OUT)") (class "Default")
      (node (ref "C24") (pin "2") (pinfunction "2_2") (pintype "passive"))
      (node (ref "C25") (pin "1") (pinfunction "1_1") (pintype "passive"))
      (node (ref "R28") (pin "2") (pinfunction "2_2") (pintype "passive"))
      (node (ref "W-AMP") (pin "7") (pinfunction "OUT_7") (pintype "output"))
    )
    (net (code "53") (name "Net-(W-AMPC-IN-)") (class "Default")
      (node (ref "C26") (pin "1") (pinfunction "1_1") (pintype "passive"))
      (node (ref "R30") (pin "1") (pinfunction "1_1") (pintype "passive"))
      (node (ref "R31") (pin "1") (pinfunction "1_1") (pintype "passive"))
      (node (ref "W-AMP") (pin "9") (pinfunction "IN-_9") (pintype "input"))
    )
    (net (code "54") (name "Net-(W-AMPC-OUT)") (class "Default")
      (node (ref "C26") (pin "2") (pinfunction "2_2") (pintype "passive"))
      (node (ref "C36") (pin "1") (pinfunction "1_1") (pintype "passive"))
      (node (ref "R31") (pin "2") (pinfunction "2_2") (pintype "passive"))
      (node (ref "W-AMP") (pin "8") (pinfunction "OUT_8") (pintype "output"))
    )
    (net (code "55") (name "Net-(W-AMPD-IN-)") (class "Default")
      (node (ref "C28") (pin "1") (pinfunction "1_1") (pintype "passive"))
      (node (ref "R32") (pin "1") (pinfunction "1_1") (pintype "passive"))
      (node (ref "R48") (pin "1") (pinfunction "1_1") (pintype "passive"))
      (node (ref "W-AMP") (pin "13") (pinfunction "IN-_13") (pintype "input"))
    )
    (net (code "56") (name "Net-(W-AMPD-OUT)") (class "Default")
      (node (ref "C28") (pin "2") (pinfunction "2_2") (pintype "passive"))
      (node (ref "D4") (pin "A") (pinfunction "A_A") (pintype "passive"))
      (node (ref "R32") (pin "2") (pinfunction "2_2") (pintype "passive"))
      (node (ref "W-AMP") (pin "14") (pinfunction "OUT_14") (pintype "output"))
    )
    (net (code "57") (name "S-OUT") (class "Default")
      (node (ref "C13") (pin "2") (pinfunction "2_2") (pintype "passive"))
      (node (ref "D2") (pin "C") (pinfunction "C_C") (pintype "passive"))
      (node (ref "JP2") (pin "4") (pinfunction "4_4") (pintype "passive"))
      (node (ref "R5") (pin "2") (pinfunction "2_2") (pintype "passive"))
    )
    (net (code "58") (name "W-OUT") (class "Default")
      (node (ref "C27") (pin "2") (pinfunction "2_2") (pintype "passive"))
      (node (ref "D4") (pin "C") (pinfunction "C_C") (pintype "passive"))
      (node (ref "JP2") (pin "5") (pinfunction "5_5") (pintype "passive"))
      (node (ref "R13") (pin "2") (pinfunction "2_2") (pintype "passive"))
    )
  )
)
